# BG_LWOC_2_1.net
KiCad netlist of a schematic drawn in EAGLE
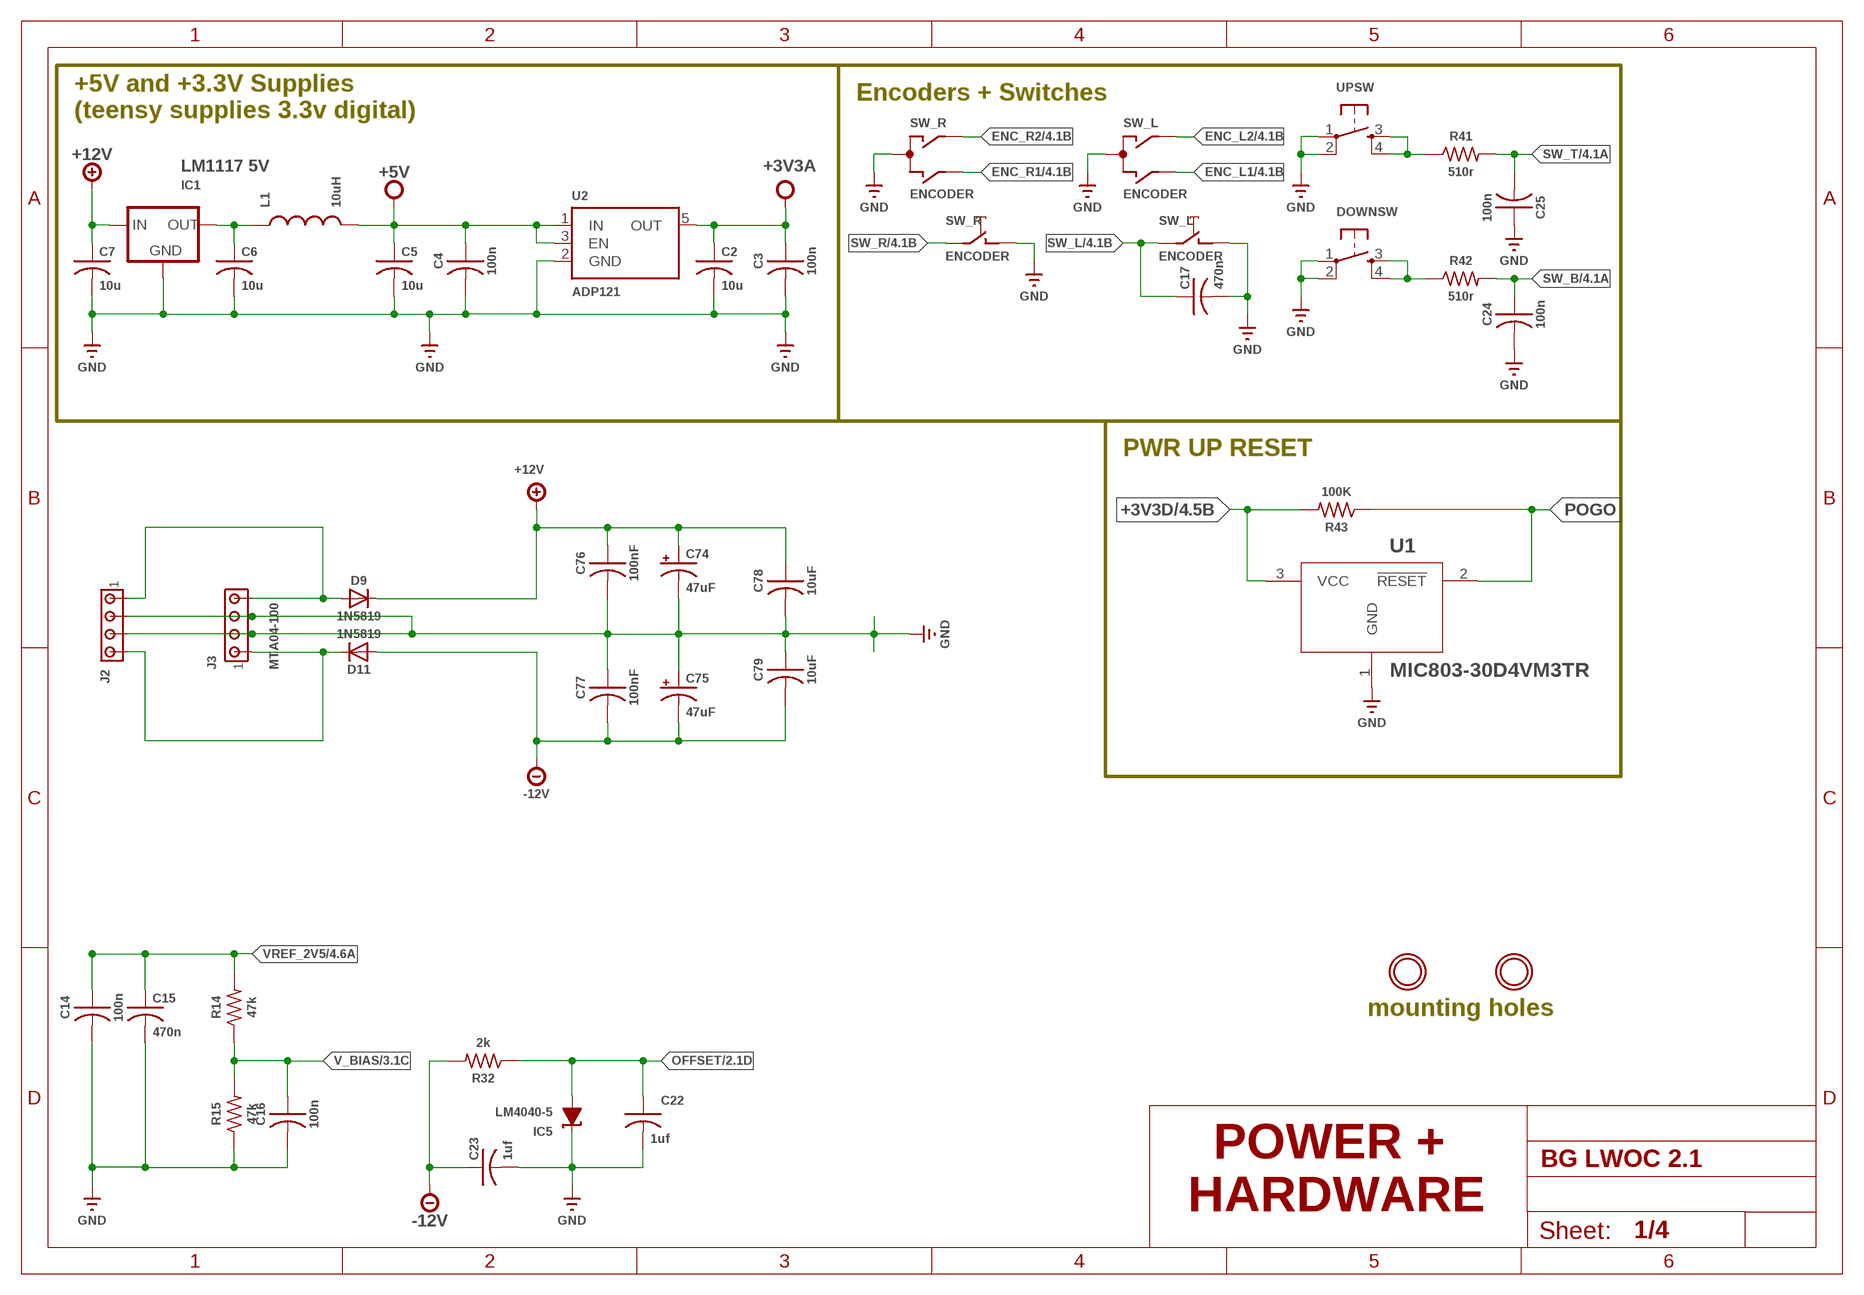
[diagram p0: schematic, sheet 1]
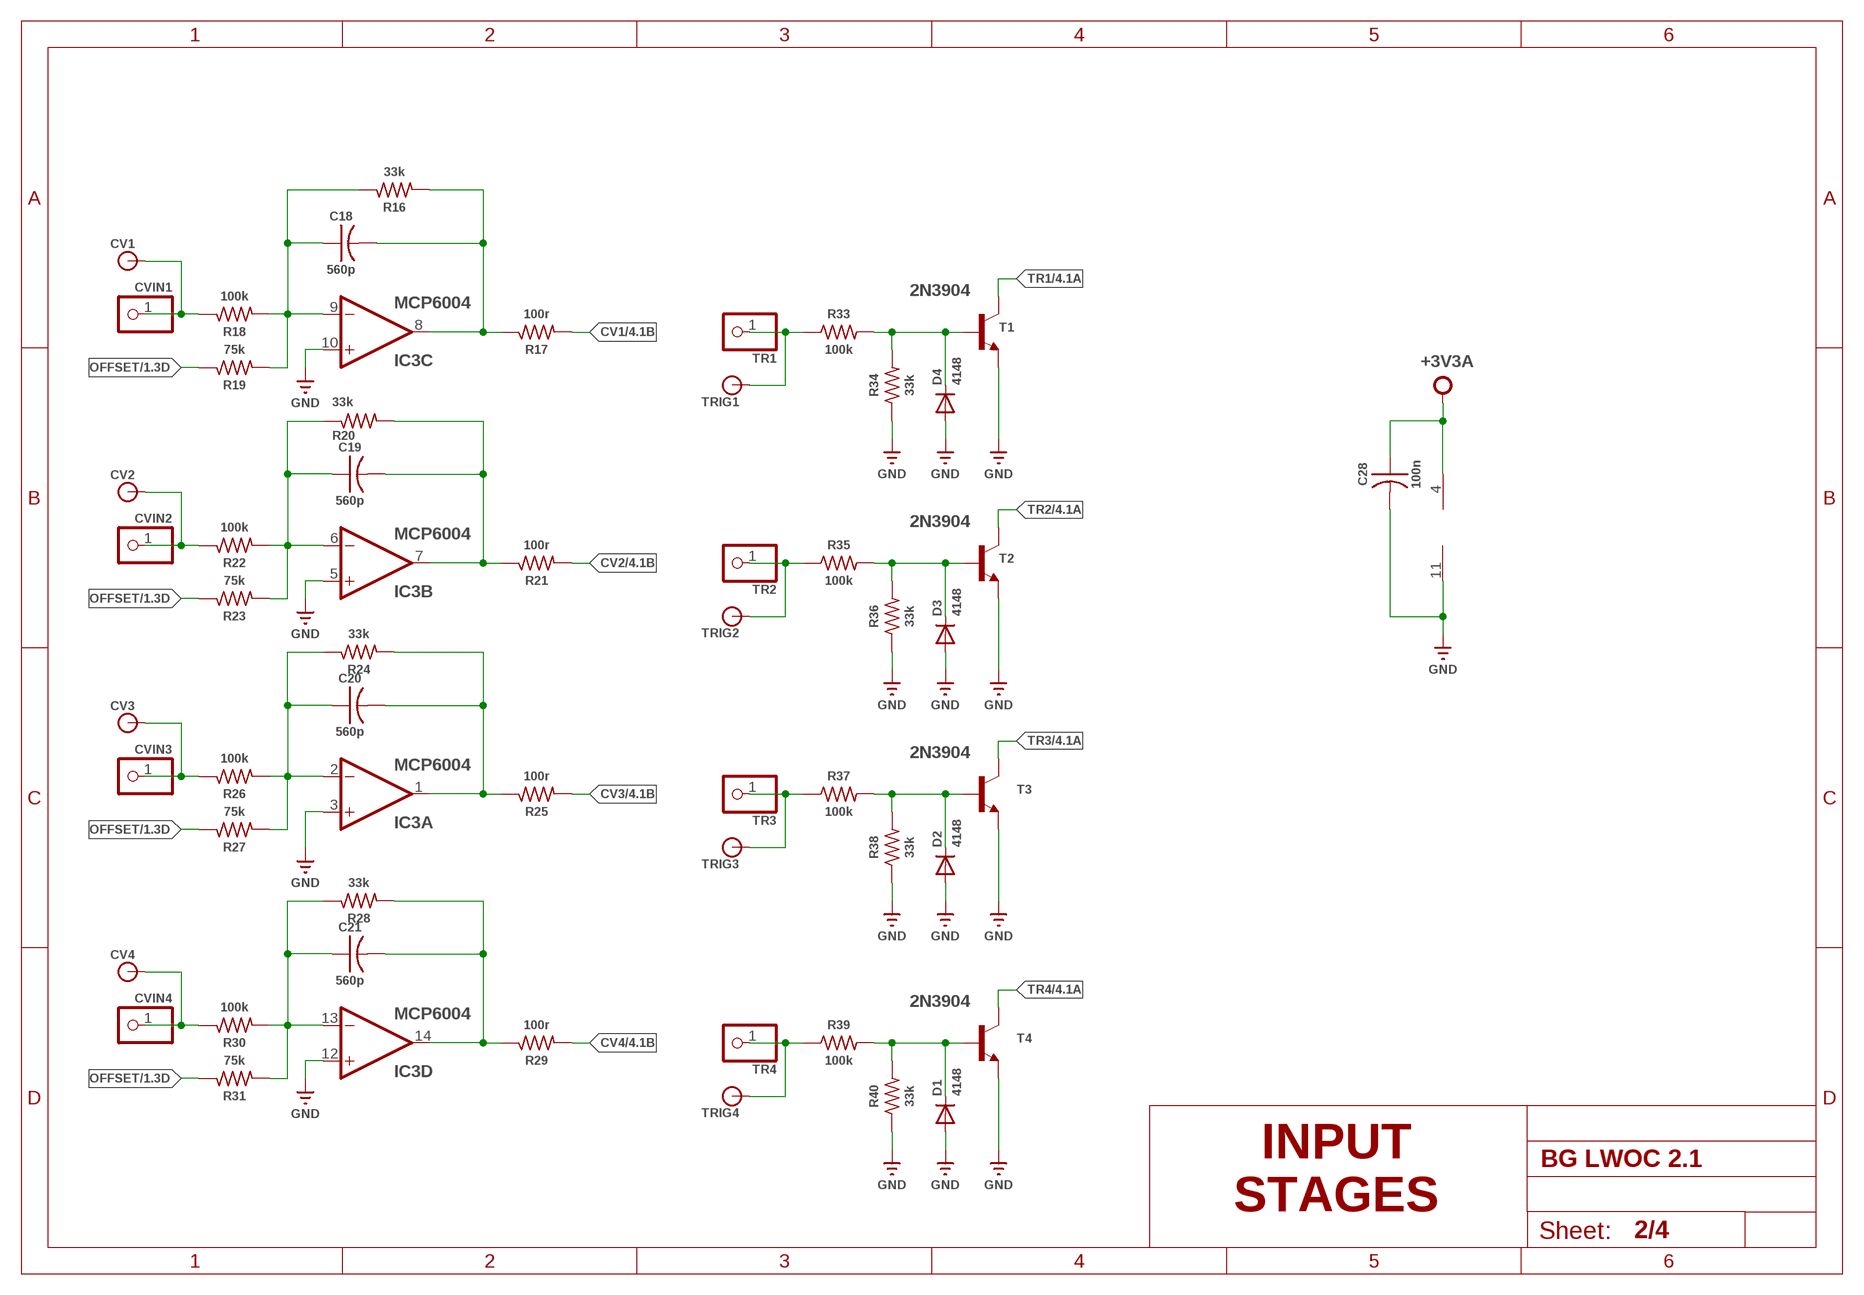
[diagram p1: schematic, sheet 2]
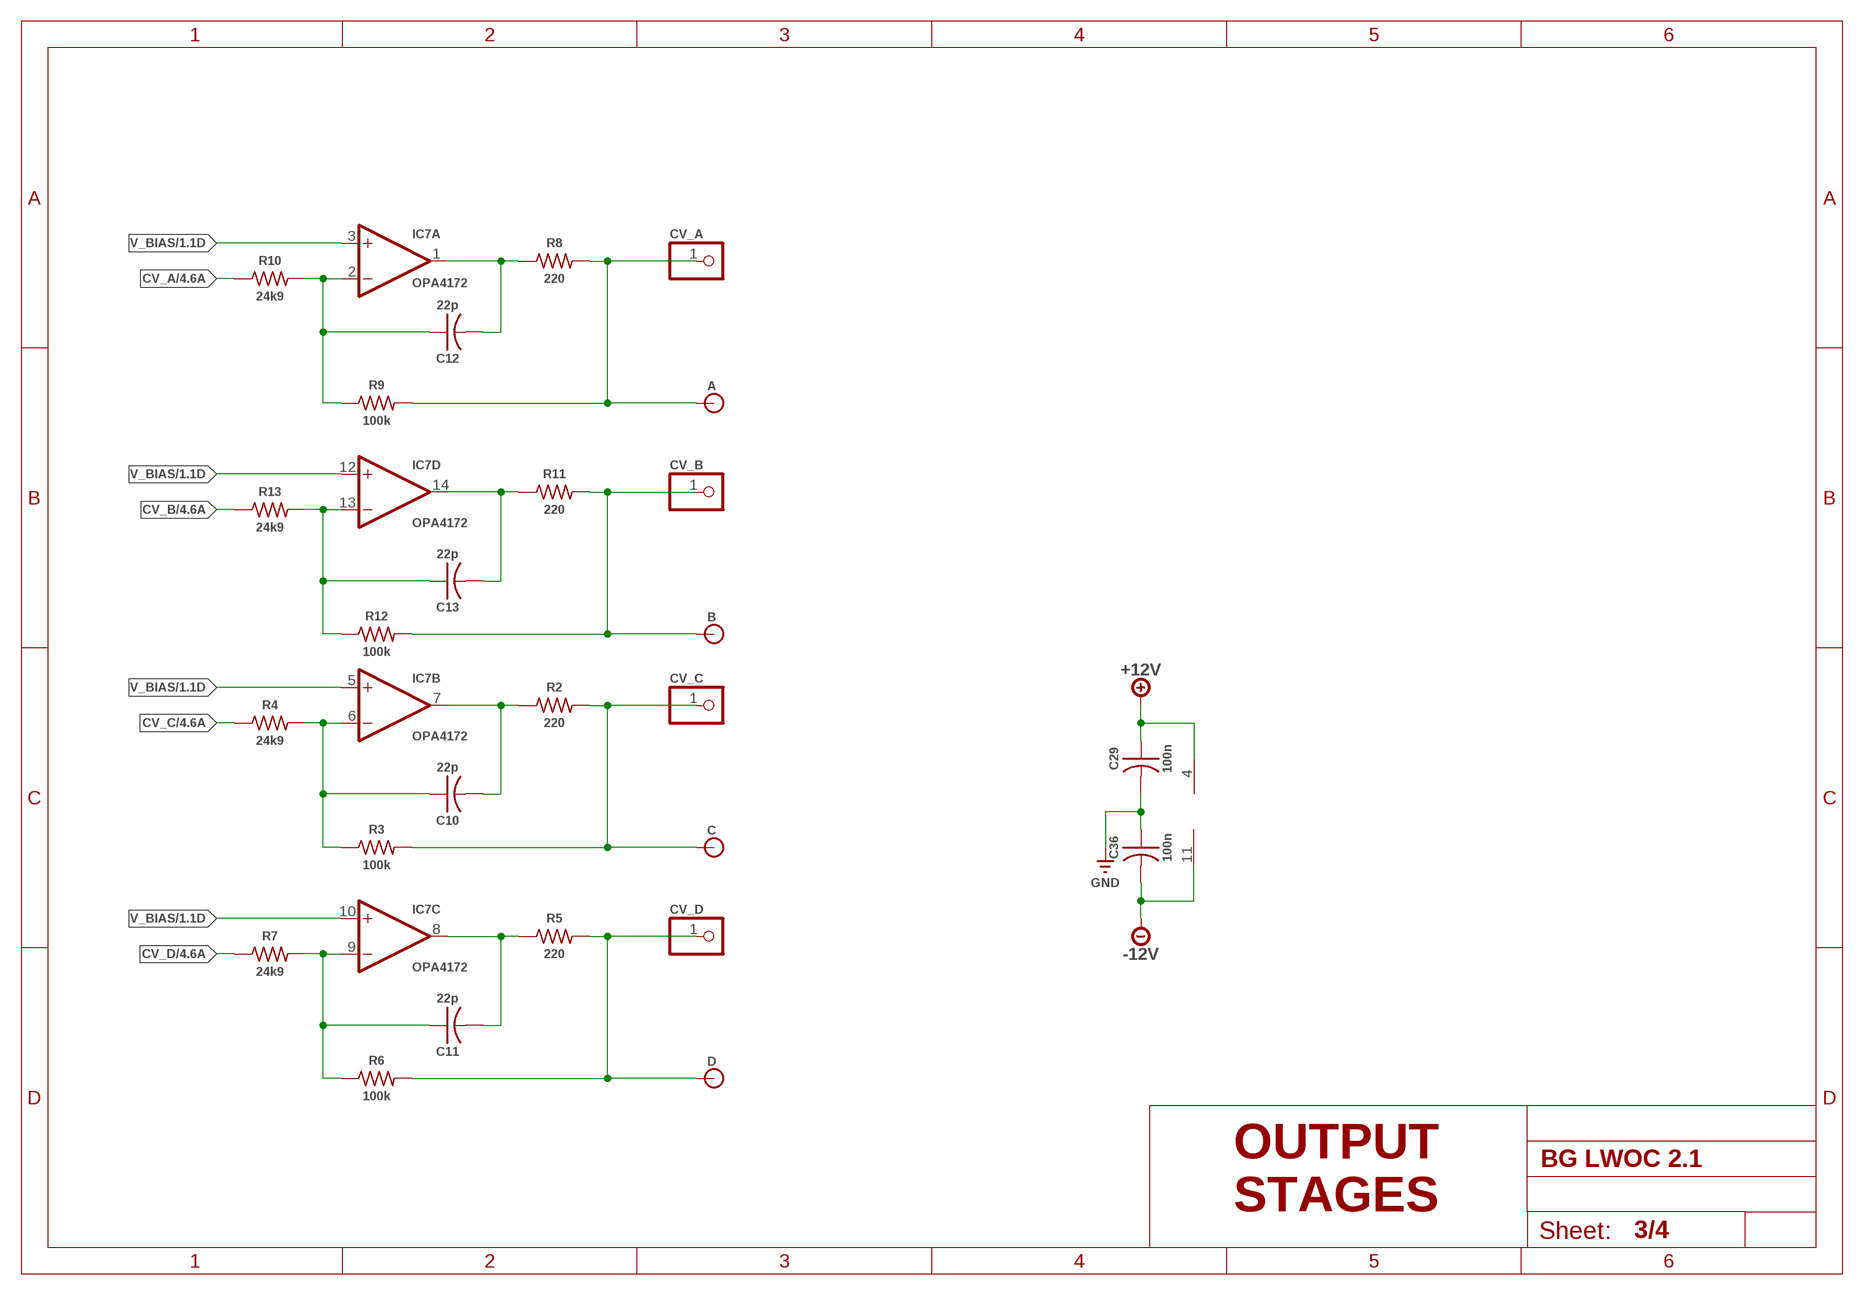
[diagram p2: schematic, sheet 3]
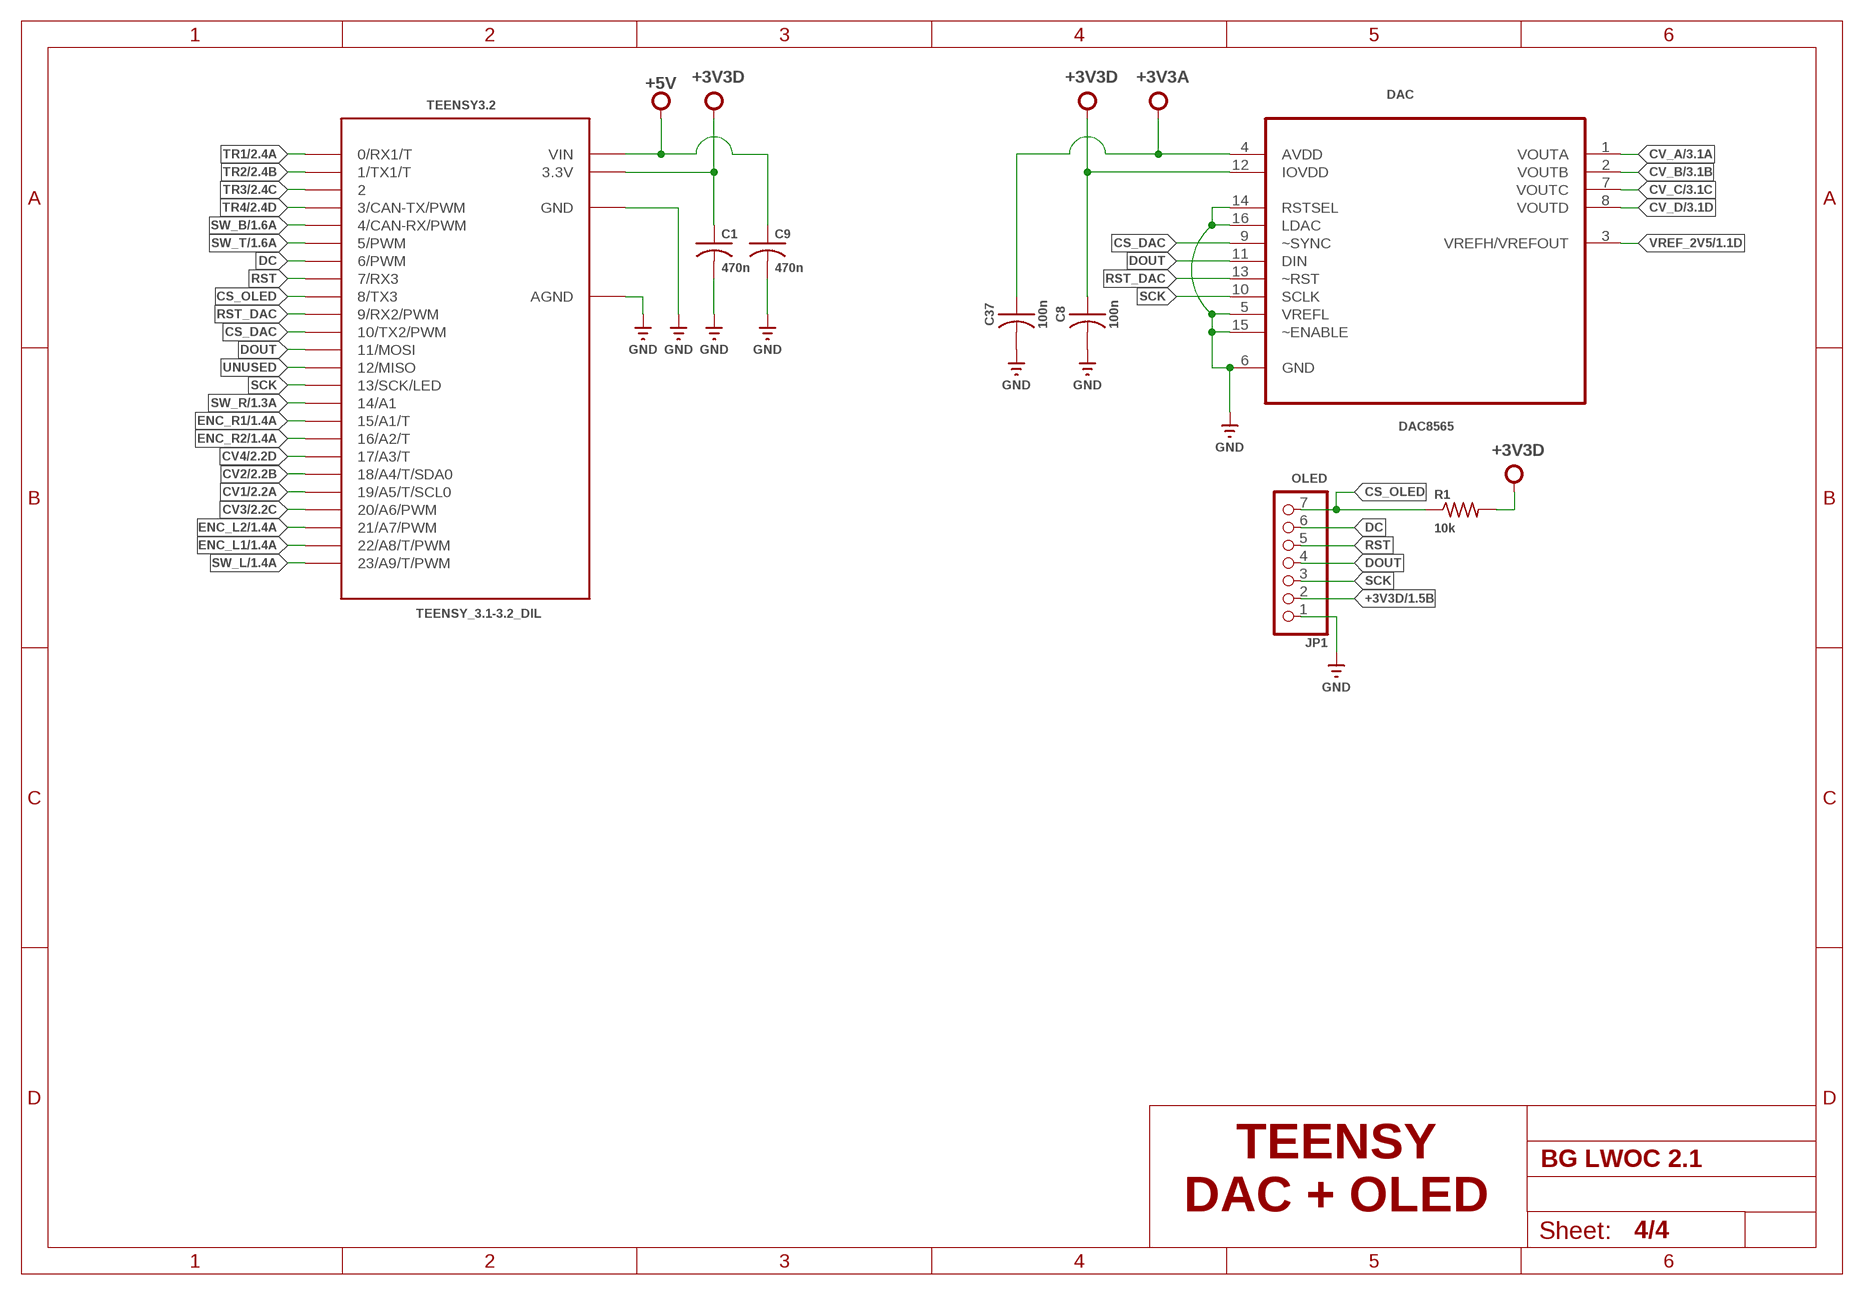
[diagram p3: schematic, sheet 4]

(export (version "E")
  (design (tool "Eeschema 10.0.6"))
  (components
    (comp (ref "C18")
      (value "560p")
      (footprint "eagle-import:RCL_C0603K")
      (libsource (lib "eagle-import") (part "RCL_C-USC0603K"))
    )
    (comp (ref "C19")
      (value "560p")
      (footprint "eagle-import:RCL_C0603K")
      (libsource (lib "eagle-import") (part "RCL_C-USC0603K"))
    )
    (comp (ref "C20")
      (value "560p")
      (footprint "eagle-import:RCL_C0603K")
      (libsource (lib "eagle-import") (part "RCL_C-USC0603K"))
    )
    (comp (ref "C21")
      (value "560p")
      (footprint "eagle-import:RCL_C0603K")
      (libsource (lib "eagle-import") (part "RCL_C-USC0603K"))
    )
    (comp (ref "C28")
      (value "100n")
      (footprint "eagle-import:RCL_C0603K")
      (libsource (lib "eagle-import") (part "RCL_C-USC0603K"))
    )
    (comp (ref "CV1")
      (value "BANANA_CONN")
      (footprint "eagle-import:BANANA_CONN")
      (libsource (lib "eagle-import") (part "BANANA_CONN"))
    )
    (comp (ref "CV2")
      (value "BANANA_CONN")
      (footprint "eagle-import:BANANA_CONN")
      (libsource (lib "eagle-import") (part "BANANA_CONN"))
    )
    (comp (ref "CV3")
      (value "BANANA_CONN")
      (footprint "eagle-import:BANANA_CONN")
      (libsource (lib "eagle-import") (part "BANANA_CONN"))
    )
    (comp (ref "CV4")
      (value "BANANA_CONN")
      (footprint "eagle-import:BANANA_CONN")
      (libsource (lib "eagle-import") (part "BANANA_CONN"))
    )
    (comp (ref "CVIN1")
      (value "PINHD-1X1")
      (footprint "eagle-import:1X01")
      (libsource (lib "eagle-import") (part "PINHD-1X1"))
    )
    (comp (ref "CVIN2")
      (value "PINHD-1X1")
      (footprint "eagle-import:1X01")
      (libsource (lib "eagle-import") (part "PINHD-1X1"))
    )
    (comp (ref "CVIN3")
      (value "PINHD-1X1")
      (footprint "eagle-import:1X01")
      (libsource (lib "eagle-import") (part "PINHD-1X1"))
    )
    (comp (ref "CVIN4")
      (value "PINHD-1X1")
      (footprint "eagle-import:1X01")
      (libsource (lib "eagle-import") (part "PINHD-1X1"))
    )
    (comp (ref "D1")
      (value "4148")
      (footprint "eagle-import:DIODE_SOD323-W")
      (libsource (lib "eagle-import") (part "DIODE_DIODE-SOD323-W"))
    )
    (comp (ref "D2")
      (value "4148")
      (footprint "eagle-import:DIODE_SOD323-W")
      (libsource (lib "eagle-import") (part "DIODE_DIODE-SOD323-W"))
    )
    (comp (ref "D3")
      (value "4148")
      (footprint "eagle-import:DIODE_SOD323-W")
      (libsource (lib "eagle-import") (part "DIODE_DIODE-SOD323-W"))
    )
    (comp (ref "D4")
      (value "4148")
      (footprint "eagle-import:DIODE_SOD323-W")
      (libsource (lib "eagle-import") (part "DIODE_DIODE-SOD323-W"))
    )
    (comp (ref "IC3")
      (value "MCP6004")
      (footprint "eagle-import:GM-ICS_SO14")
      (libsource (lib "eagle-import") (part "GM-ICS_TL074D"))
    )
    (comp (ref "R16")
      (value "33k")
      (footprint "eagle-import:RCL_R0603")
      (libsource (lib "eagle-import") (part "RCL_R-US_R0603"))
    )
    (comp (ref "R17")
      (value "100r")
      (footprint "eagle-import:RCL_R0603")
      (libsource (lib "eagle-import") (part "RCL_R-US_R0603"))
    )
    (comp (ref "R18")
      (value "100k")
      (footprint "eagle-import:RCL_R0603")
      (libsource (lib "eagle-import") (part "RCL_R-US_R0603"))
    )
    (comp (ref "R19")
      (value "75k")
      (footprint "eagle-import:RCL_R0603")
      (libsource (lib "eagle-import") (part "RCL_R-US_R0603"))
    )
    (comp (ref "R20")
      (value "33k")
      (footprint "eagle-import:RCL_R0603")
      (libsource (lib "eagle-import") (part "RCL_R-US_R0603"))
    )
    (comp (ref "R21")
      (value "100r")
      (footprint "eagle-import:RCL_R0603")
      (libsource (lib "eagle-import") (part "RCL_R-US_R0603"))
    )
    (comp (ref "R22")
      (value "100k")
      (footprint "eagle-import:RCL_R0603")
      (libsource (lib "eagle-import") (part "RCL_R-US_R0603"))
    )
    (comp (ref "R23")
      (value "75k")
      (footprint "eagle-import:RCL_R0603")
      (libsource (lib "eagle-import") (part "RCL_R-US_R0603"))
    )
    (comp (ref "R24")
      (value "33k")
      (footprint "eagle-import:RCL_R0603")
      (libsource (lib "eagle-import") (part "RCL_R-US_R0603"))
    )
    (comp (ref "R25")
      (value "100r")
      (footprint "eagle-import:RCL_R0603")
      (libsource (lib "eagle-import") (part "RCL_R-US_R0603"))
    )
    (comp (ref "R26")
      (value "100k")
      (footprint "eagle-import:RCL_R0603")
      (libsource (lib "eagle-import") (part "RCL_R-US_R0603"))
    )
    (comp (ref "R27")
      (value "75k")
      (footprint "eagle-import:RCL_R0603")
      (libsource (lib "eagle-import") (part "RCL_R-US_R0603"))
    )
    (comp (ref "R28")
      (value "33k")
      (footprint "eagle-import:RCL_R0603")
      (libsource (lib "eagle-import") (part "RCL_R-US_R0603"))
    )
    (comp (ref "R29")
      (value "100r")
      (footprint "eagle-import:RCL_R0603")
      (libsource (lib "eagle-import") (part "RCL_R-US_R0603"))
    )
    (comp (ref "R30")
      (value "100k")
      (footprint "eagle-import:RCL_R0603")
      (libsource (lib "eagle-import") (part "RCL_R-US_R0603"))
    )
    (comp (ref "R31")
      (value "75k")
      (footprint "eagle-import:RCL_R0603")
      (libsource (lib "eagle-import") (part "RCL_R-US_R0603"))
    )
    (comp (ref "R33")
      (value "100k")
      (footprint "eagle-import:RCL_R0603")
      (libsource (lib "eagle-import") (part "RCL_R-US_R0603"))
    )
    (comp (ref "R34")
      (value "33k")
      (footprint "eagle-import:RCL_R0603")
      (libsource (lib "eagle-import") (part "RCL_R-US_R0603"))
    )
    (comp (ref "R35")
      (value "100k")
      (footprint "eagle-import:RCL_R0603")
      (libsource (lib "eagle-import") (part "RCL_R-US_R0603"))
    )
    (comp (ref "R36")
      (value "33k")
      (footprint "eagle-import:RCL_R0603")
      (libsource (lib "eagle-import") (part "RCL_R-US_R0603"))
    )
    (comp (ref "R37")
      (value "100k")
      (footprint "eagle-import:RCL_R0603")
      (libsource (lib "eagle-import") (part "RCL_R-US_R0603"))
    )
    (comp (ref "R38")
      (value "33k")
      (footprint "eagle-import:RCL_R0603")
      (libsource (lib "eagle-import") (part "RCL_R-US_R0603"))
    )
    (comp (ref "R39")
      (value "100k")
      (footprint "eagle-import:RCL_R0603")
      (libsource (lib "eagle-import") (part "RCL_R-US_R0603"))
    )
    (comp (ref "R40")
      (value "33k")
      (footprint "eagle-import:RCL_R0603")
      (libsource (lib "eagle-import") (part "RCL_R-US_R0603"))
    )
    (comp (ref "T1")
      (value "2N3904")
      (footprint "eagle-import:TRANSISTOR_SOT23-BEC")
      (libsource (lib "eagle-import") (part "TRANSISTOR_-NPN-SOT23-BECMMBT3904LT1"))
    )
    (comp (ref "T2")
      (value "2N3904")
      (footprint "eagle-import:TRANSISTOR_SOT23-BEC")
      (libsource (lib "eagle-import") (part "TRANSISTOR_-NPN-SOT23-BECMMBT3904LT1"))
    )
    (comp (ref "T3")
      (value "2N3904")
      (footprint "eagle-import:TRANSISTOR_SOT23-BEC")
      (libsource (lib "eagle-import") (part "TRANSISTOR_-NPN-SOT23-BECMMBT3904LT1"))
    )
    (comp (ref "T4")
      (value "2N3904")
      (footprint "eagle-import:TRANSISTOR_SOT23-BEC")
      (libsource (lib "eagle-import") (part "TRANSISTOR_-NPN-SOT23-BECMMBT3904LT1"))
    )
    (comp (ref "TR1")
      (value "PINHD-1X1")
      (footprint "eagle-import:1X01")
      (libsource (lib "eagle-import") (part "PINHD-1X1"))
    )
    (comp (ref "TR2")
      (value "PINHD-1X1")
      (footprint "eagle-import:1X01")
      (libsource (lib "eagle-import") (part "PINHD-1X1"))
    )
    (comp (ref "TR3")
      (value "PINHD-1X1")
      (footprint "eagle-import:1X01")
      (libsource (lib "eagle-import") (part "PINHD-1X1"))
    )
    (comp (ref "TR4")
      (value "PINHD-1X1")
      (footprint "eagle-import:1X01")
      (libsource (lib "eagle-import") (part "PINHD-1X1"))
    )
    (comp (ref "TRIG1")
      (value "BANANA_CONN")
      (footprint "eagle-import:BANANA_CONN")
      (libsource (lib "eagle-import") (part "BANANA_CONN"))
    )
    (comp (ref "TRIG2")
      (value "BANANA_CONN")
      (footprint "eagle-import:BANANA_CONN")
      (libsource (lib "eagle-import") (part "BANANA_CONN"))
    )
    (comp (ref "TRIG3")
      (value "BANANA_CONN")
      (footprint "eagle-import:BANANA_CONN")
      (libsource (lib "eagle-import") (part "BANANA_CONN"))
    )
    (comp (ref "TRIG4")
      (value "BANANA_CONN")
      (footprint "eagle-import:BANANA_CONN")
      (libsource (lib "eagle-import") (part "BANANA_CONN"))
    )
    (comp (ref "A")
      (value "BANANA_CONN")
      (footprint "eagle-import:BANANA_CONN")
      (libsource (lib "eagle-import") (part "BANANA_CONN"))
    )
    (comp (ref "B")
      (value "BANANA_CONN")
      (footprint "eagle-import:BANANA_CONN")
      (libsource (lib "eagle-import") (part "BANANA_CONN"))
    )
    (comp (ref "C")
      (value "BANANA_CONN")
      (footprint "eagle-import:BANANA_CONN")
      (libsource (lib "eagle-import") (part "BANANA_CONN"))
    )
    (comp (ref "C10")
      (value "22p")
      (footprint "eagle-import:RCL_C0603K")
      (libsource (lib "eagle-import") (part "RCL_C-USC0603K"))
    )
    (comp (ref "C11")
      (value "22p")
      (footprint "eagle-import:RCL_C0603K")
      (libsource (lib "eagle-import") (part "RCL_C-USC0603K"))
    )
    (comp (ref "C12")
      (value "22p")
      (footprint "eagle-import:RCL_C0603K")
      (libsource (lib "eagle-import") (part "RCL_C-USC0603K"))
    )
    (comp (ref "C13")
      (value "22p")
      (footprint "eagle-import:RCL_C0603K")
      (libsource (lib "eagle-import") (part "RCL_C-USC0603K"))
    )
    (comp (ref "C29")
      (value "100n")
      (footprint "eagle-import:RCL_C0603K")
      (libsource (lib "eagle-import") (part "RCL_C-USC0603K"))
    )
    (comp (ref "C36")
      (value "100n")
      (footprint "eagle-import:RCL_C0603K")
      (libsource (lib "eagle-import") (part "RCL_C-USC0603K"))
    )
    (comp (ref "CV_A")
      (value "PINHD-1X1")
      (footprint "eagle-import:1X01")
      (libsource (lib "eagle-import") (part "PINHD-1X1"))
    )
    (comp (ref "CV_B")
      (value "PINHD-1X1")
      (footprint "eagle-import:1X01")
      (libsource (lib "eagle-import") (part "PINHD-1X1"))
    )
    (comp (ref "CV_C")
      (value "PINHD-1X1")
      (footprint "eagle-import:1X01")
      (libsource (lib "eagle-import") (part "PINHD-1X1"))
    )
    (comp (ref "CV_D")
      (value "PINHD-1X1")
      (footprint "eagle-import:1X01")
      (libsource (lib "eagle-import") (part "PINHD-1X1"))
    )
    (comp (ref "D")
      (value "BANANA_CONN")
      (footprint "eagle-import:BANANA_CONN")
      (libsource (lib "eagle-import") (part "BANANA_CONN"))
    )
    (comp (ref "IC7")
      (value "OPA4172")
      (footprint "eagle-import:GM-ICS_SO14")
      (libsource (lib "eagle-import") (part "GM-ICS_TL074D"))
    )
    (comp (ref "R2")
      (value "220")
      (footprint "eagle-import:RCL_R0603")
      (libsource (lib "eagle-import") (part "RCL_R-US_R0603"))
    )
    (comp (ref "R3")
      (value "100k")
      (footprint "eagle-import:RCL_R0603")
      (libsource (lib "eagle-import") (part "RCL_R-US_R0603"))
    )
    (comp (ref "R4")
      (value "24k9")
      (footprint "eagle-import:RCL_R0603")
      (libsource (lib "eagle-import") (part "RCL_R-US_R0603"))
    )
    (comp (ref "R5")
      (value "220")
      (footprint "eagle-import:RCL_R0603")
      (libsource (lib "eagle-import") (part "RCL_R-US_R0603"))
    )
    (comp (ref "R6")
      (value "100k")
      (footprint "eagle-import:RCL_R0603")
      (libsource (lib "eagle-import") (part "RCL_R-US_R0603"))
    )
    (comp (ref "R7")
      (value "24k9")
      (footprint "eagle-import:RCL_R0603")
      (libsource (lib "eagle-import") (part "RCL_R-US_R0603"))
    )
    (comp (ref "R8")
      (value "220")
      (footprint "eagle-import:RCL_R0603")
      (libsource (lib "eagle-import") (part "RCL_R-US_R0603"))
    )
    (comp (ref "R9")
      (value "100k")
      (footprint "eagle-import:RCL_R0603")
      (libsource (lib "eagle-import") (part "RCL_R-US_R0603"))
    )
    (comp (ref "R10")
      (value "24k9")
      (footprint "eagle-import:RCL_R0603")
      (libsource (lib "eagle-import") (part "RCL_R-US_R0603"))
    )
    (comp (ref "R11")
      (value "220")
      (footprint "eagle-import:RCL_R0603")
      (libsource (lib "eagle-import") (part "RCL_R-US_R0603"))
    )
    (comp (ref "R12")
      (value "100k")
      (footprint "eagle-import:RCL_R0603")
      (libsource (lib "eagle-import") (part "RCL_R-US_R0603"))
    )
    (comp (ref "R13")
      (value "24k9")
      (footprint "eagle-import:RCL_R0603")
      (libsource (lib "eagle-import") (part "RCL_R-US_R0603"))
    )
    (comp (ref "C2")
      (value "10u")
      (footprint "eagle-import:C1206K")
      (libsource (lib "eagle-import") (part "C-USC1206K"))
    )
    (comp (ref "C3")
      (value "100n")
      (footprint "eagle-import:RCL_C0603K")
      (libsource (lib "eagle-import") (part "RCL_C-USC0603K"))
    )
    (comp (ref "C4")
      (value "100n")
      (footprint "eagle-import:RCL_C0603K")
      (libsource (lib "eagle-import") (part "RCL_C-USC0603K"))
    )
    (comp (ref "C5")
      (value "10u")
      (footprint "eagle-import:C1206K")
      (libsource (lib "eagle-import") (part "C-USC1206K"))
    )
    (comp (ref "C6")
      (value "10u")
      (footprint "eagle-import:C1206K")
      (libsource (lib "eagle-import") (part "C-USC1206K"))
    )
    (comp (ref "C7")
      (value "10u")
      (footprint "eagle-import:C1206K")
      (libsource (lib "eagle-import") (part "C-USC1206K"))
    )
    (comp (ref "C14")
      (value "100n")
      (footprint "eagle-import:RCL_C0603K")
      (libsource (lib "eagle-import") (part "RCL_C-USC0603K"))
    )
    (comp (ref "C15")
      (value "470n")
      (footprint "eagle-import:RCL_C0603K")
      (libsource (lib "eagle-import") (part "RCL_C-USC0603K"))
    )
    (comp (ref "C16")
      (value "100n")
      (footprint "eagle-import:RCL_C0603K")
      (libsource (lib "eagle-import") (part "RCL_C-USC0603K"))
    )
    (comp (ref "C17")
      (value "470n")
      (footprint "eagle-import:C0805K")
      (libsource (lib "eagle-import") (part "C-USC0805K"))
    )
    (comp (ref "C22")
      (value "1uf")
      (footprint "eagle-import:C0805K")
      (libsource (lib "eagle-import") (part "C-USC0805K"))
    )
    (comp (ref "C23")
      (value "1uf")
      (footprint "eagle-import:C0805K")
      (libsource (lib "eagle-import") (part "C-USC0805K"))
    )
    (comp (ref "C24")
      (value "100n")
      (footprint "eagle-import:RCL_C0603K")
      (libsource (lib "eagle-import") (part "RCL_C-USC0603K"))
    )
    (comp (ref "C25")
      (value "100n")
      (footprint "eagle-import:RCL_C0603K")
      (libsource (lib "eagle-import") (part "RCL_C-USC0603K"))
    )
    (comp (ref "C74")
      (value "47uF")
      (footprint "eagle-import:RCL_E2,5-6")
      (libsource (lib "eagle-import") (part "RCL_CPOL-USE2.5-6"))
    )
    (comp (ref "C75")
      (value "47uF")
      (footprint "eagle-import:RCL_E2,5-6")
      (libsource (lib "eagle-import") (part "RCL_CPOL-USE2.5-6"))
    )
    (comp (ref "C76")
      (value "100nF")
      (footprint "eagle-import:RCL_C0603K")
      (libsource (lib "eagle-import") (part "ripples_v40_RCL_C-USC0603K"))
    )
    (comp (ref "C77")
      (value "100nF")
      (footprint "eagle-import:RCL_C0603K")
      (libsource (lib "eagle-import") (part "ripples_v40_RCL_C-USC0603K"))
    )
    (comp (ref "C78")
      (value "10uF")
      (footprint "eagle-import:RCL_C1210")
      (libsource (lib "eagle-import") (part "RCL_C-USC1210"))
    )
    (comp (ref "C79")
      (value "10uF")
      (footprint "eagle-import:RCL_C1210")
      (libsource (lib "eagle-import") (part "RCL_C-USC1210"))
    )
    (comp (ref "D9")
      (value "1N5819")
      (footprint "eagle-import:DIODE_SOD323-W")
      (libsource (lib "eagle-import") (part "ripples_v40_DIODE_DIODE-SOD323-W"))
    )
    (comp (ref "D11")
      (value "1N5819")
      (footprint "eagle-import:DIODE_SOD323-W")
      (libsource (lib "eagle-import") (part "ripples_v40_DIODE_DIODE-SOD323-W"))
    )
    (comp (ref "DOWNSW")
      (value "SPARKFUN_TAC_SWITCHPTH")
      (footprint "eagle-import:SPARKFUN_TACTILE-PTH")
      (libsource (lib "eagle-import") (part "SPARKFUN_TAC_SWITCHPTH"))
    )
    (comp (ref "IC1")
      (value "LM1117 5V")
      (footprint "eagle-import:TO252")
      (libsource (lib "eagle-import") (part "LM1117TO252"))
    )
    (comp (ref "IC5")
      (value "LM4040-5")
      (footprint "eagle-import:DBZ_R-PDSO-G3")
      (libsource (lib "eagle-import") (part "LM4041DBZA12"))
    )
    (comp (ref "J2")
      (value "MTA04-156")
      (footprint "eagle-import:1X4MTA")
      (libsource (lib "eagle-import") (part "MTA04-156"))
    )
    (comp (ref "J3")
      (value "MTA04-100")
      (footprint "eagle-import:1X04MTA")
      (libsource (lib "eagle-import") (part "MTA04-100"))
    )
    (comp (ref "L1")
      (value "10uH")
      (footprint "eagle-import:1210")
      (libsource (lib "eagle-import") (part "INDUCTOR1210"))
    )
    (comp (ref "R14")
      (value "47k")
      (footprint "eagle-import:RCL_R0603")
      (libsource (lib "eagle-import") (part "RCL_R-US_R0603"))
    )
    (comp (ref "R15")
      (value "47k")
      (footprint "eagle-import:RCL_R0603")
      (libsource (lib "eagle-import") (part "RCL_R-US_R0603"))
    )
    (comp (ref "R32")
      (value "2k")
      (footprint "eagle-import:RCL_R0603")
      (libsource (lib "eagle-import") (part "RCL_R-US_R0603"))
    )
    (comp (ref "R41")
      (value "510r")
      (footprint "eagle-import:RCL_R0603")
      (libsource (lib "eagle-import") (part "RCL_R-US_R0603"))
    )
    (comp (ref "R42")
      (value "510r")
      (footprint "eagle-import:RCL_R0603")
      (libsource (lib "eagle-import") (part "RCL_R-US_R0603"))
    )
    (comp (ref "R43")
      (value "100K")
      (footprint "eagle-import:RCL_R0603")
      (libsource (lib "eagle-import") (part "RCL_R-US_R0603"))
    )
    (comp (ref "SW_L")
      (value "ENCODER")
      (footprint "eagle-import:OG-ENCODER_ALPS_EC12E_SW")
      (libsource (lib "eagle-import") (part "OG-ENCODER_EC12E_SW"))
    )
    (comp (ref "SW_R")
      (value "ENCODER")
      (footprint "eagle-import:OG-ENCODER_ALPS_EC12E_SW")
      (libsource (lib "eagle-import") (part "OG-ENCODER_EC12E_SW"))
    )
    (comp (ref "U$23")
      (value "MOUNTINGHOLE2.5")
      (footprint "eagle-import:MOUNTINGHOLE_2.5_PLATED")
      (libsource (lib "eagle-import") (part "MOUNTINGHOLE2.5"))
    )
    (comp (ref "U$26")
      (value "MOUNTINGHOLE2.5")
      (footprint "eagle-import:MOUNTINGHOLE_2.5_PLATED")
      (libsource (lib "eagle-import") (part "MOUNTINGHOLE2.5"))
    )
    (comp (ref "U1")
      (value "MIC803-30D4VM3TR")
      (footprint "eagle-import:SOT95P232X110-3N")
      (libsource (lib "eagle-import") (part "MIC803-30D4VM3TR"))
    )
    (comp (ref "U2")
      (value "ADP121")
      (footprint "eagle-import:SOT23-5")
      (libsource (lib "eagle-import") (part "ADP121"))
    )
    (comp (ref "UPSW")
      (value "SPARKFUN_TAC_SWITCHPTH")
      (footprint "eagle-import:SPARKFUN_TACTILE-PTH")
      (libsource (lib "eagle-import") (part "SPARKFUN_TAC_SWITCHPTH"))
    )
    (comp (ref "C1")
      (value "470n")
      (footprint "eagle-import:C0805K")
      (libsource (lib "eagle-import") (part "C-USC0805K"))
    )
    (comp (ref "C8")
      (value "100n")
      (footprint "eagle-import:RCL_C0603K")
      (libsource (lib "eagle-import") (part "RCL_C-USC0603K"))
    )
    (comp (ref "C9")
      (value "470n")
      (footprint "eagle-import:C0805K")
      (libsource (lib "eagle-import") (part "C-USC0805K"))
    )
    (comp (ref "C37")
      (value "100n")
      (footprint "eagle-import:RCL_C0603K")
      (libsource (lib "eagle-import") (part "RCL_C-USC0603K"))
    )
    (comp (ref "DAC")
      (value "DAC8565")
      (footprint "eagle-import:SOP65P640X120-16N")
      (fields (field (name "MF") "Texas Instruments") (field (name "MP") "DAC8565IAPW"))
      (libsource (lib "eagle-import") (part "DAC8565IAPW"))
    )
    (comp (ref "JP1")
      (value "OLED")
      (footprint "eagle-import:1X07")
      (libsource (lib "eagle-import") (part "PINHD-1X7"))
    )
    (comp (ref "R1")
      (value "10k")
      (footprint "eagle-import:M0805")
      (libsource (lib "eagle-import") (part "R-US_M0805"))
    )
    (comp (ref "TEENSY3.2")
      (value "TEENSY_3.1-3.2_DIL")
      (footprint "eagle-import:TEENSY_3.0-3.2&LC_DIL")
      (libsource (lib "eagle-import") (part "TEENSY_3.1-3.2_DIL"))
    )
  )
  (nets
    (net (code "1") (name "+3V3A") (class "Default")
      (node (ref "C2") (pin "1") (pinfunction "1_1") (pintype "passive"))
      (node (ref "C28") (pin "1") (pinfunction "1_1") (pintype "passive"))
      (node (ref "C3") (pin "1") (pinfunction "1_1") (pintype "passive"))
      (node (ref "C37") (pin "1") (pinfunction "1_1") (pintype "passive"))
      (node (ref "DAC") (pin "4") (pinfunction "AVDD_4") (pintype "power_in"))
      (node (ref "IC3") (pin "4") (pinfunction "V+_4") (pintype "power_in"))
      (node (ref "U2") (pin "5") (pinfunction "OUT_5") (pintype "bidirectional"))
    )
    (net (code "2") (name "+3V3D") (class "Default")
      (node (ref "C1") (pin "1") (pinfunction "1_1") (pintype "passive"))
      (node (ref "C8") (pin "1") (pinfunction "1_1") (pintype "passive"))
      (node (ref "DAC") (pin "12") (pinfunction "IOVDD_12") (pintype "power_in"))
      (node (ref "JP1") (pin "2") (pinfunction "2_2") (pintype "passive"))
      (node (ref "R1") (pin "2") (pinfunction "2_2") (pintype "passive"))
      (node (ref "R43") (pin "2") (pinfunction "2_2") (pintype "passive"))
      (node (ref "TEENSY3.2") (pin "3.3V") (pinfunction "3.3V_3.3V") (pintype "power_in"))
      (node (ref "U1") (pin "3") (pinfunction "VCC_3") (pintype "power_in"))
    )
    (net (code "3") (name "+5V") (class "Default")
      (node (ref "C4") (pin "1") (pinfunction "1_1") (pintype "passive"))
      (node (ref "C5") (pin "1") (pinfunction "1_1") (pintype "passive"))
      (node (ref "C9") (pin "1") (pinfunction "1_1") (pintype "passive"))
      (node (ref "L1") (pin "2") (pinfunction "2_2") (pintype "passive"))
      (node (ref "TEENSY3.2") (pin "VIN") (pinfunction "VIN_VIN") (pintype "power_in"))
      (node (ref "U2") (pin "1") (pinfunction "IN_1") (pintype "bidirectional"))
      (node (ref "U2") (pin "3") (pinfunction "EN_3") (pintype "bidirectional"))
    )
    (net (code "4") (name "+12V") (class "Default")
      (node (ref "C29") (pin "1") (pinfunction "1_1") (pintype "passive"))
      (node (ref "C7") (pin "1") (pinfunction "1_1") (pintype "passive"))
      (node (ref "C74") (pin "+") (pinfunction "+_+") (pintype "passive"))
      (node (ref "C76") (pin "1") (pinfunction "1_1") (pintype "passive"))
      (node (ref "C78") (pin "1") (pinfunction "1_1") (pintype "passive"))
      (node (ref "D9") (pin "C") (pinfunction "C_C") (pintype "passive"))
      (node (ref "IC1") (pin "2") (pinfunction "IN_2") (pintype "input"))
      (node (ref "IC7") (pin "4") (pinfunction "V+_4") (pintype "power_in"))
    )
    (net (code "5") (name "-12V") (class "Default")
      (node (ref "C23") (pin "1") (pinfunction "1_1") (pintype "passive"))
      (node (ref "C36") (pin "2") (pinfunction "2_2") (pintype "passive"))
      (node (ref "C75") (pin "-") (pinfunction "-_-") (pintype "passive"))
      (node (ref "C77") (pin "2") (pinfunction "2_2") (pintype "passive"))
      (node (ref "C79") (pin "2") (pinfunction "2_2") (pintype "passive"))
      (node (ref "D11") (pin "A") (pinfunction "A_A") (pintype "passive"))
      (node (ref "IC7") (pin "11") (pinfunction "V-_11") (pintype "power_in"))
      (node (ref "R32") (pin "2") (pinfunction "2_2") (pintype "passive"))
    )
    (net (code "6") (name "CS_DAC") (class "Default")
      (node (ref "DAC") (pin "9") (pinfunction "~{SYNC}_9") (pintype "input"))
      (node (ref "TEENSY3.2") (pin "10") (pinfunction "10/TX2/PWM_10") (pintype "bidirectional"))
    )
    (net (code "7") (name "CS_OLED") (class "Default")
      (node (ref "JP1") (pin "7") (pinfunction "7_7") (pintype "passive"))
      (node (ref "R1") (pin "1") (pinfunction "1_1") (pintype "passive"))
      (node (ref "TEENSY3.2") (pin "8") (pinfunction "8/TX3_8") (pintype "bidirectional"))
    )
    (net (code "8") (name "CV1") (class "Default")
      (node (ref "R17") (pin "2") (pinfunction "2_2") (pintype "passive"))
      (node (ref "TEENSY3.2") (pin "19/A5") (pinfunction "19/A5/T/SCL0_19/A5") (pintype "bidirectional"))
    )
    (net (code "9") (name "CV2") (class "Default")
      (node (ref "R21") (pin "2") (pinfunction "2_2") (pintype "passive"))
      (node (ref "TEENSY3.2") (pin "18/A4") (pinfunction "18/A4/T/SDA0_18/A4") (pintype "bidirectional"))
    )
    (net (code "10") (name "CV3") (class "Default")
      (node (ref "R25") (pin "2") (pinfunction "2_2") (pintype "passive"))
      (node (ref "TEENSY3.2") (pin "20/A6") (pinfunction "20/A6/PWM_20/A6") (pintype "bidirectional"))
    )
    (net (code "11") (name "CV4") (class "Default")
      (node (ref "R29") (pin "2") (pinfunction "2_2") (pintype "passive"))
      (node (ref "TEENSY3.2") (pin "17/A3") (pinfunction "17/A3/T_17/A3") (pintype "bidirectional"))
    )
    (net (code "12") (name "CV_A") (class "Default")
      (node (ref "DAC") (pin "1") (pinfunction "VOUTA_1") (pintype "output"))
      (node (ref "R10") (pin "1") (pinfunction "1_1") (pintype "passive"))
    )
    (net (code "13") (name "CV_B") (class "Default")
      (node (ref "DAC") (pin "2") (pinfunction "VOUTB_2") (pintype "output"))
      (node (ref "R13") (pin "1") (pinfunction "1_1") (pintype "passive"))
    )
    (net (code "14") (name "CV_C") (class "Default")
      (node (ref "DAC") (pin "7") (pinfunction "VOUTC_7") (pintype "output"))
      (node (ref "R4") (pin "1") (pinfunction "1_1") (pintype "passive"))
    )
    (net (code "15") (name "CV_D") (class "Default")
      (node (ref "DAC") (pin "8") (pinfunction "VOUTD_8") (pintype "output"))
      (node (ref "R7") (pin "1") (pinfunction "1_1") (pintype "passive"))
    )
    (net (code "16") (name "DC") (class "Default")
      (node (ref "JP1") (pin "6") (pinfunction "6_6") (pintype "passive"))
      (node (ref "TEENSY3.2") (pin "6") (pinfunction "6/PWM_6") (pintype "bidirectional"))
    )
    (net (code "17") (name "DOUT") (class "Default")
      (node (ref "DAC") (pin "11") (pinfunction "DIN_11") (pintype "input"))
      (node (ref "JP1") (pin "4") (pinfunction "4_4") (pintype "passive"))
      (node (ref "TEENSY3.2") (pin "11") (pinfunction "11/MOSI_11") (pintype "bidirectional"))
    )
    (net (code "18") (name "ENC_L1") (class "Default")
      (node (ref "SW_L") (pin "B") (pinfunction "B_B") (pintype "passive"))
      (node (ref "TEENSY3.2") (pin "22/A8") (pinfunction "22/A8/T/PWM_22/A8") (pintype "bidirectional"))
    )
    (net (code "19") (name "ENC_L2") (class "Default")
      (node (ref "SW_L") (pin "A") (pinfunction "A_A") (pintype "passive"))
      (node (ref "TEENSY3.2") (pin "21/A7") (pinfunction "21/A7/PWM_21/A7") (pintype "bidirectional"))
    )
    (net (code "20") (name "ENC_R1") (class "Default")
      (node (ref "SW_R") (pin "B") (pinfunction "B_B") (pintype "passive"))
      (node (ref "TEENSY3.2") (pin "15/A1") (pinfunction "15/A1/T_15/A1") (pintype "bidirectional"))
    )
    (net (code "21") (name "ENC_R2") (class "Default")
      (node (ref "SW_R") (pin "A") (pinfunction "A_A") (pintype "passive"))
      (node (ref "TEENSY3.2") (pin "16/A2") (pinfunction "16/A2/T_16/A2") (pintype "bidirectional"))
    )
    (net (code "22") (name "GND") (class "Default")
      (node (ref "C1") (pin "2") (pinfunction "2_2") (pintype "passive"))
      (node (ref "C14") (pin "2") (pinfunction "2_2") (pintype "passive"))
      (node (ref "C15") (pin "2") (pinfunction "2_2") (pintype "passive"))
      (node (ref "C16") (pin "2") (pinfunction "2_2") (pintype "passive"))
      (node (ref "C17") (pin "2") (pinfunction "2_2") (pintype "passive"))
      (node (ref "C2") (pin "2") (pinfunction "2_2") (pintype "passive"))
      (node (ref "C22") (pin "2") (pinfunction "2_2") (pintype "passive"))
      (node (ref "C23") (pin "2") (pinfunction "2_2") (pintype "passive"))
      (node (ref "C24") (pin "2") (pinfunction "2_2") (pintype "passive"))
      (node (ref "C25") (pin "1") (pinfunction "1_1") (pintype "passive"))
      (node (ref "C28") (pin "2") (pinfunction "2_2") (pintype "passive"))
      (node (ref "C29") (pin "2") (pinfunction "2_2") (pintype "passive"))
      (node (ref "C3") (pin "2") (pinfunction "2_2") (pintype "passive"))
      (node (ref "C36") (pin "1") (pinfunction "1_1") (pintype "passive"))
      (node (ref "C37") (pin "2") (pinfunction "2_2") (pintype "passive"))
      (node (ref "C4") (pin "2") (pinfunction "2_2") (pintype "passive"))
      (node (ref "C5") (pin "2") (pinfunction "2_2") (pintype "passive"))
      (node (ref "C6") (pin "2") (pinfunction "2_2") (pintype "passive"))
      (node (ref "C7") (pin "2") (pinfunction "2_2") (pintype "passive"))
      (node (ref "C74") (pin "-") (pinfunction "-_-") (pintype "passive"))
      (node (ref "C75") (pin "+") (pinfunction "+_+") (pintype "passive"))
      (node (ref "C76") (pin "2") (pinfunction "2_2") (pintype "passive"))
      (node (ref "C77") (pin "1") (pinfunction "1_1") (pintype "passive"))
      (node (ref "C78") (pin "2") (pinfunction "2_2") (pintype "passive"))
      (node (ref "C79") (pin "1") (pinfunction "1_1") (pintype "passive"))
      (node (ref "C8") (pin "2") (pinfunction "2_2") (pintype "passive"))
      (node (ref "C9") (pin "2") (pinfunction "2_2") (pintype "passive"))
      (node (ref "D1") (pin "A") (pinfunction "A_A") (pintype "passive"))
      (node (ref "D2") (pin "A") (pinfunction "A_A") (pintype "passive"))
      (node (ref "D3") (pin "A") (pinfunction "A_A") (pintype "passive"))
      (node (ref "D4") (pin "A") (pinfunction "A_A") (pintype "passive"))
      (node (ref "DAC") (pin "14") (pinfunction "RSTSEL_14") (pintype "input"))
      (node (ref "DAC") (pin "15") (pinfunction "~{ENABLE}_15") (pintype "input"))
      (node (ref "DAC") (pin "16") (pinfunction "LDAC_16") (pintype "input"))
      (node (ref "DAC") (pin "5") (pinfunction "VREFL_5") (pintype "input"))
      (node (ref "DAC") (pin "6") (pinfunction "GND_6") (pintype "passive"))
      (node (ref "DOWNSW") (pin "1") (pinfunction "1_1") (pintype "passive"))
      (node (ref "DOWNSW") (pin "2") (pinfunction "2_2") (pintype "passive"))
      (node (ref "IC1") (pin "1") (pinfunction "GND_1") (pintype "input"))
      (node (ref "IC3") (pin "10") (pinfunction "+IN_10") (pintype "input"))
      (node (ref "IC3") (pin "11") (pinfunction "V-_11") (pintype "power_in"))
      (node (ref "IC3") (pin "12") (pinfunction "+IN_12") (pintype "input"))
      (node (ref "IC3") (pin "3") (pinfunction "+IN_3") (pintype "input"))
      (node (ref "IC3") (pin "5") (pinfunction "+IN_5") (pintype "input"))
      (node (ref "IC5") (pin "1") (pinfunction "C_1") (pintype "passive"))
      (node (ref "J2") (pin "2") (pinfunction "2_2") (pintype "passive"))
      (node (ref "J2") (pin "3") (pinfunction "3_3") (pintype "passive"))
      (node (ref "J3") (pin "2") (pinfunction "3_2") (pintype "bidirectional"))
      (node (ref "J3") (pin "3") (pinfunction "2_3") (pintype "bidirectional"))
      (node (ref "JP1") (pin "1") (pinfunction "1_1") (pintype "passive"))
      (node (ref "R15") (pin "1") (pinfunction "1_1") (pintype "passive"))
      (node (ref "R34") (pin "1") (pinfunction "1_1") (pintype "passive"))
      (node (ref "R36") (pin "1") (pinfunction "1_1") (pintype "passive"))
      (node (ref "R38") (pin "1") (pinfunction "1_1") (pintype "passive"))
      (node (ref "R40") (pin "1") (pinfunction "1_1") (pintype "passive"))
      (node (ref "SW_L") (pin "C") (pinfunction "C_C") (pintype "passive"))
      (node (ref "SW_L") (pin "D") (pinfunction "1_D") (pintype "passive"))
      (node (ref "SW_R") (pin "C") (pinfunction "C_C") (pintype "passive"))
      (node (ref "SW_R") (pin "D") (pinfunction "1_D") (pintype "passive"))
      (node (ref "T1") (pin "E") (pinfunction "E_E") (pintype "passive"))
      (node (ref "T2") (pin "E") (pinfunction "E_E") (pintype "passive"))
      (node (ref "T3") (pin "E") (pinfunction "E_E") (pintype "passive"))
      (node (ref "T4") (pin "E") (pinfunction "E_E") (pintype "passive"))
      (node (ref "TEENSY3.2") (pin "AGND") (pinfunction "AGND_AGND") (pintype "power_in"))
      (node (ref "TEENSY3.2") (pin "GND") (pinfunction "GND_GND") (pintype "power_in"))
      (node (ref "U1") (pin "1") (pinfunction "GND_1") (pintype "passive"))
      (node (ref "U2") (pin "2") (pinfunction "GND_2") (pintype "bidirectional"))
      (node (ref "UPSW") (pin "1") (pinfunction "1_1") (pintype "passive"))
      (node (ref "UPSW") (pin "2") (pinfunction "2_2") (pintype "passive"))
    )
    (net (code "23") (name "Net-(A-1)") (class "Default")
      (node (ref "A") (pin "P$1") (pinfunction "1_P$1") (pintype "passive"))
      (node (ref "CV_A") (pin "1") (pinfunction "1_1") (pintype "passive"))
      (node (ref "R8") (pin "2") (pinfunction "2_2") (pintype "passive"))
      (node (ref "R9") (pin "2") (pinfunction "2_2") (pintype "passive"))
    )
    (net (code "24") (name "Net-(B-1)") (class "Default")
      (node (ref "B") (pin "P$1") (pinfunction "1_P$1") (pintype "passive"))
      (node (ref "CV_B") (pin "1") (pinfunction "1_1") (pintype "passive"))
      (node (ref "R11") (pin "2") (pinfunction "2_2") (pintype "passive"))
      (node (ref "R12") (pin "2") (pinfunction "2_2") (pintype "passive"))
    )
    (net (code "25") (name "Net-(C-1)") (class "Default")
      (node (ref "C") (pin "P$1") (pinfunction "1_P$1") (pintype "passive"))
      (node (ref "CV_C") (pin "1") (pinfunction "1_1") (pintype "passive"))
      (node (ref "R2") (pin "2") (pinfunction "2_2") (pintype "passive"))
      (node (ref "R3") (pin "2") (pinfunction "2_2") (pintype "passive"))
    )
    (net (code "26") (name "Net-(CV1-1)") (class "Default")
      (node (ref "CV1") (pin "P$1") (pinfunction "1_P$1") (pintype "passive"))
      (node (ref "CVIN1") (pin "1") (pinfunction "1_1") (pintype "passive"))
      (node (ref "R18") (pin "1") (pinfunction "1_1") (pintype "passive"))
    )
    (net (code "27") (name "Net-(CV2-1)") (class "Default")
      (node (ref "CV2") (pin "P$1") (pinfunction "1_P$1") (pintype "passive"))
      (node (ref "CVIN2") (pin "1") (pinfunction "1_1") (pintype "passive"))
      (node (ref "R22") (pin "1") (pinfunction "1_1") (pintype "passive"))
    )
    (net (code "28") (name "Net-(CV3-1)") (class "Default")
      (node (ref "CV3") (pin "P$1") (pinfunction "1_P$1") (pintype "passive"))
      (node (ref "CVIN3") (pin "1") (pinfunction "1_1") (pintype "passive"))
      (node (ref "R26") (pin "1") (pinfunction "1_1") (pintype "passive"))
    )
    (net (code "29") (name "Net-(CV4-1)") (class "Default")
      (node (ref "CV4") (pin "P$1") (pinfunction "1_P$1") (pintype "passive"))
      (node (ref "CVIN4") (pin "1") (pinfunction "1_1") (pintype "passive"))
      (node (ref "R30") (pin "1") (pinfunction "1_1") (pintype "passive"))
    )
    (net (code "30") (name "Net-(D-1)") (class "Default")
      (node (ref "CV_D") (pin "1") (pinfunction "1_1") (pintype "passive"))
      (node (ref "D") (pin "P$1") (pinfunction "1_P$1") (pintype "passive"))
      (node (ref "R5") (pin "2") (pinfunction "2_2") (pintype "passive"))
      (node (ref "R6") (pin "2") (pinfunction "2_2") (pintype "passive"))
    )
    (net (code "31") (name "Net-(D1-PadC)") (class "Default")
      (node (ref "D1") (pin "C") (pinfunction "C_C") (pintype "passive"))
      (node (ref "R39") (pin "2") (pinfunction "2_2") (pintype "passive"))
      (node (ref "R40") (pin "2") (pinfunction "2_2") (pintype "passive"))
      (node (ref "T4") (pin "B") (pinfunction "B_B") (pintype "passive"))
    )
    (net (code "32") (name "Net-(D2-PadC)") (class "Default")
      (node (ref "D2") (pin "C") (pinfunction "C_C") (pintype "passive"))
      (node (ref "R37") (pin "2") (pinfunction "2_2") (pintype "passive"))
      (node (ref "R38") (pin "2") (pinfunction "2_2") (pintype "passive"))
      (node (ref "T3") (pin "B") (pinfunction "B_B") (pintype "passive"))
    )
    (net (code "33") (name "Net-(D3-PadC)") (class "Default")
      (node (ref "D3") (pin "C") (pinfunction "C_C") (pintype "passive"))
      (node (ref "R35") (pin "2") (pinfunction "2_2") (pintype "passive"))
      (node (ref "R36") (pin "2") (pinfunction "2_2") (pintype "passive"))
      (node (ref "T2") (pin "B") (pinfunction "B_B") (pintype "passive"))
    )
    (net (code "34") (name "Net-(D4-PadC)") (class "Default")
      (node (ref "D4") (pin "C") (pinfunction "C_C") (pintype "passive"))
      (node (ref "R33") (pin "2") (pinfunction "2_2") (pintype "passive"))
      (node (ref "R34") (pin "2") (pinfunction "2_2") (pintype "passive"))
      (node (ref "T1") (pin "B") (pinfunction "B_B") (pintype "passive"))
    )
    (net (code "35") (name "Net-(DOWNSW-Pad3)") (class "Default")
      (node (ref "DOWNSW") (pin "3") (pinfunction "3_3") (pintype "passive"))
      (node (ref "DOWNSW") (pin "4") (pinfunction "4_4") (pintype "passive"))
      (node (ref "R42") (pin "1") (pinfunction "1_1") (pintype "passive"))
    )
    (net (code "36") (name "Net-(IC1-OUT)") (class "Default")
      (node (ref "C6") (pin "1") (pinfunction "1_1") (pintype "passive"))
      (node (ref "IC1") (pin "3") (pinfunction "OUT_3") (pintype "passive"))
      (node (ref "L1") (pin "1") (pinfunction "1_1") (pintype "passive"))
    )
    (net (code "37") (name "Net-(IC3A--IN)") (class "Default")
      (node (ref "C20") (pin "1") (pinfunction "1_1") (pintype "passive"))
      (node (ref "IC3") (pin "2") (pinfunction "-IN_2") (pintype "input"))
      (node (ref "R24") (pin "1") (pinfunction "1_1") (pintype "passive"))
      (node (ref "R26") (pin "2") (pinfunction "2_2") (pintype "passive"))
      (node (ref "R27") (pin "2") (pinfunction "2_2") (pintype "passive"))
    )
    (net (code "38") (name "Net-(IC3A-OUT)") (class "Default")
      (node (ref "C20") (pin "2") (pinfunction "2_2") (pintype "passive"))
      (node (ref "IC3") (pin "1") (pinfunction "OUT_1") (pintype "output"))
      (node (ref "R24") (pin "2") (pinfunction "2_2") (pintype "passive"))
      (node (ref "R25") (pin "1") (pinfunction "1_1") (pintype "passive"))
    )
    (net (code "39") (name "Net-(IC3B--IN)") (class "Default")
      (node (ref "C19") (pin "1") (pinfunction "1_1") (pintype "passive"))
      (node (ref "IC3") (pin "6") (pinfunction "-IN_6") (pintype "input"))
      (node (ref "R20") (pin "1") (pinfunction "1_1") (pintype "passive"))
      (node (ref "R22") (pin "2") (pinfunction "2_2") (pintype "passive"))
      (node (ref "R23") (pin "2") (pinfunction "2_2") (pintype "passive"))
    )
    (net (code "40") (name "Net-(IC3B-OUT)") (class "Default")
      (node (ref "C19") (pin "2") (pinfunction "2_2") (pintype "passive"))
      (node (ref "IC3") (pin "7") (pinfunction "OUT_7") (pintype "output"))
      (node (ref "R20") (pin "2") (pinfunction "2_2") (pintype "passive"))
      (node (ref "R21") (pin "1") (pinfunction "1_1") (pintype "passive"))
    )
    (net (code "41") (name "Net-(IC3C--IN)") (class "Default")
      (node (ref "C18") (pin "1") (pinfunction "1_1") (pintype "passive"))
      (node (ref "IC3") (pin "9") (pinfunction "-IN_9") (pintype "input"))
      (node (ref "R16") (pin "1") (pinfunction "1_1") (pintype "passive"))
      (node (ref "R18") (pin "2") (pinfunction "2_2") (pintype "passive"))
      (node (ref "R19") (pin "2") (pinfunction "2_2") (pintype "passive"))
    )
    (net (code "42") (name "Net-(IC3C-OUT)") (class "Default")
      (node (ref "C18") (pin "2") (pinfunction "2_2") (pintype "passive"))
      (node (ref "IC3") (pin "8") (pinfunction "OUT_8") (pintype "output"))
      (node (ref "R16") (pin "2") (pinfunction "2_2") (pintype "passive"))
      (node (ref "R17") (pin "1") (pinfunction "1_1") (pintype "passive"))
    )
    (net (code "43") (name "Net-(IC3D--IN)") (class "Default")
      (node (ref "C21") (pin "1") (pinfunction "1_1") (pintype "passive"))
      (node (ref "IC3") (pin "13") (pinfunction "-IN_13") (pintype "input"))
      (node (ref "R28") (pin "1") (pinfunction "1_1") (pintype "passive"))
      (node (ref "R30") (pin "2") (pinfunction "2_2") (pintype "passive"))
      (node (ref "R31") (pin "2") (pinfunction "2_2") (pintype "passive"))
    )
    (net (code "44") (name "Net-(IC3D-OUT)") (class "Default")
      (node (ref "C21") (pin "2") (pinfunction "2_2") (pintype "passive"))
      (node (ref "IC3") (pin "14") (pinfunction "OUT_14") (pintype "output"))
      (node (ref "R28") (pin "2") (pinfunction "2_2") (pintype "passive"))
      (node (ref "R29") (pin "1") (pinfunction "1_1") (pintype "passive"))
    )
    (net (code "45") (name "Net-(IC7A--IN)") (class "Default")
      (node (ref "C12") (pin "1") (pinfunction "1_1") (pintype "passive"))
      (node (ref "IC7") (pin "2") (pinfunction "-IN_2") (pintype "input"))
      (node (ref "R10") (pin "2") (pinfunction "2_2") (pintype "passive"))
      (node (ref "R9") (pin "1") (pinfunction "1_1") (pintype "passive"))
    )
    (net (code "46") (name "Net-(IC7A-OUT)") (class "Default")
      (node (ref "C12") (pin "2") (pinfunction "2_2") (pintype "passive"))
      (node (ref "IC7") (pin "1") (pinfunction "OUT_1") (pintype "output"))
      (node (ref "R8") (pin "1") (pinfunction "1_1") (pintype "passive"))
    )
    (net (code "47") (name "Net-(IC7B--IN)") (class "Default")
      (node (ref "C10") (pin "1") (pinfunction "1_1") (pintype "passive"))
      (node (ref "IC7") (pin "6") (pinfunction "-IN_6") (pintype "input"))
      (node (ref "R3") (pin "1") (pinfunction "1_1") (pintype "passive"))
      (node (ref "R4") (pin "2") (pinfunction "2_2") (pintype "passive"))
    )
    (net (code "48") (name "Net-(IC7B-OUT)") (class "Default")
      (node (ref "C10") (pin "2") (pinfunction "2_2") (pintype "passive"))
      (node (ref "IC7") (pin "7") (pinfunction "OUT_7") (pintype "output"))
      (node (ref "R2") (pin "1") (pinfunction "1_1") (pintype "passive"))
    )
    (net (code "49") (name "Net-(IC7C--IN)") (class "Default")
      (node (ref "C11") (pin "1") (pinfunction "1_1") (pintype "passive"))
      (node (ref "IC7") (pin "9") (pinfunction "-IN_9") (pintype "input"))
      (node (ref "R6") (pin "1") (pinfunction "1_1") (pintype "passive"))
      (node (ref "R7") (pin "2") (pinfunction "2_2") (pintype "passive"))
    )
    (net (code "50") (name "Net-(IC7C-OUT)") (class "Default")
      (node (ref "C11") (pin "2") (pinfunction "2_2") (pintype "passive"))
      (node (ref "IC7") (pin "8") (pinfunction "OUT_8") (pintype "output"))
      (node (ref "R5") (pin "1") (pinfunction "1_1") (pintype "passive"))
    )
    (net (code "51") (name "Net-(IC7D--IN)") (class "Default")
      (node (ref "C13") (pin "1") (pinfunction "1_1") (pintype "passive"))
      (node (ref "IC7") (pin "13") (pinfunction "-IN_13") (pintype "input"))
      (node (ref "R12") (pin "1") (pinfunction "1_1") (pintype "passive"))
      (node (ref "R13") (pin "2") (pinfunction "2_2") (pintype "passive"))
    )
    (net (code "52") (name "Net-(IC7D-OUT)") (class "Default")
      (node (ref "C13") (pin "2") (pinfunction "2_2") (pintype "passive"))
      (node (ref "IC7") (pin "14") (pinfunction "OUT_14") (pintype "output"))
      (node (ref "R11") (pin "1") (pinfunction "1_1") (pintype "passive"))
    )
    (net (code "53") (name "Net-(J3-1)") (class "Default")
      (node (ref "D11") (pin "C") (pinfunction "C_C") (pintype "passive"))
      (node (ref "J2") (pin "4") (pinfunction "4_4") (pintype "passive"))
      (node (ref "J3") (pin "4") (pinfunction "1_4") (pintype "bidirectional"))
    )
    (net (code "54") (name "Net-(J3-4)") (class "Default")
      (node (ref "D9") (pin "A") (pinfunction "A_A") (pintype "passive"))
      (node (ref "J2") (pin "1") (pinfunction "1_1") (pintype "passive"))
      (node (ref "J3") (pin "1") (pinfunction "4_1") (pintype "bidirectional"))
    )
    (net (code "55") (name "Net-(R41-Pad1)") (class "Default")
      (node (ref "R41") (pin "1") (pinfunction "1_1") (pintype "passive"))
      (node (ref "UPSW") (pin "3") (pinfunction "3_3") (pintype "passive"))
      (node (ref "UPSW") (pin "4") (pinfunction "4_4") (pintype "passive"))
    )
    (net (code "56") (name "Net-(TRIG1-1)") (class "Default")
      (node (ref "R33") (pin "1") (pinfunction "1_1") (pintype "passive"))
      (node (ref "TR1") (pin "1") (pinfunction "1_1") (pintype "passive"))
      (node (ref "TRIG1") (pin "P$1") (pinfunction "1_P$1") (pintype "passive"))
    )
    (net (code "57") (name "Net-(TRIG2-1)") (class "Default")
      (node (ref "R35") (pin "1") (pinfunction "1_1") (pintype "passive"))
      (node (ref "TR2") (pin "1") (pinfunction "1_1") (pintype "passive"))
      (node (ref "TRIG2") (pin "P$1") (pinfunction "1_P$1") (pintype "passive"))
    )
    (net (code "58") (name "Net-(TRIG3-1)") (class "Default")
      (node (ref "R37") (pin "1") (pinfunction "1_1") (pintype "passive"))
      (node (ref "TR3") (pin "1") (pinfunction "1_1") (pintype "passive"))
      (node (ref "TRIG3") (pin "P$1") (pinfunction "1_P$1") (pintype "passive"))
    )
    (net (code "59") (name "Net-(TRIG4-1)") (class "Default")
      (node (ref "R39") (pin "1") (pinfunction "1_1") (pintype "passive"))
      (node (ref "TR4") (pin "1") (pinfunction "1_1") (pintype "passive"))
      (node (ref "TRIG4") (pin "P$1") (pinfunction "1_P$1") (pintype "passive"))
    )
    (net (code "60") (name "OFFSET") (class "Default")
      (node (ref "C22") (pin "1") (pinfunction "1_1") (pintype "passive"))
      (node (ref "IC5") (pin "2") (pinfunction "A_2") (pintype "passive"))
      (node (ref "R19") (pin "1") (pinfunction "1_1") (pintype "passive"))
      (node (ref "R23") (pin "1") (pinfunction "1_1") (pintype "passive"))
      (node (ref "R27") (pin "1") (pinfunction "1_1") (pintype "passive"))
      (node (ref "R31") (pin "1") (pinfunction "1_1") (pintype "passive"))
      (node (ref "R32") (pin "1") (pinfunction "1_1") (pintype "passive"))
    )
    (net (code "61") (name "POGO") (class "Default")
      (node (ref "R43") (pin "1") (pinfunction "1_1") (pintype "passive"))
      (node (ref "U1") (pin "2") (pinfunction "~{RESET}_2") (pintype "passive"))
    )
    (net (code "62") (name "RST") (class "Default")
      (node (ref "JP1") (pin "5") (pinfunction "5_5") (pintype "passive"))
      (node (ref "TEENSY3.2") (pin "7") (pinfunction "7/RX3_7") (pintype "bidirectional"))
    )
    (net (code "63") (name "RST_DAC") (class "Default")
      (node (ref "DAC") (pin "13") (pinfunction "~{RST}_13") (pintype "input"))
      (node (ref "TEENSY3.2") (pin "9") (pinfunction "9/RX2/PWM_9") (pintype "bidirectional"))
    )
    (net (code "64") (name "SCK") (class "Default")
      (node (ref "DAC") (pin "10") (pinfunction "SCLK_10") (pintype "input"))
      (node (ref "JP1") (pin "3") (pinfunction "3_3") (pintype "passive"))
      (node (ref "TEENSY3.2") (pin "13") (pinfunction "13/SCK/LED_13") (pintype "bidirectional"))
    )
    (net (code "65") (name "SW_B") (class "Default")
      (node (ref "C24") (pin "1") (pinfunction "1_1") (pintype "passive"))
      (node (ref "R42") (pin "2") (pinfunction "2_2") (pintype "passive"))
      (node (ref "TEENSY3.2") (pin "4") (pinfunction "4/CAN-RX/PWM_4") (pintype "bidirectional"))
    )
    (net (code "66") (name "SW_L") (class "Default")
      (node (ref "C17") (pin "1") (pinfunction "1_1") (pintype "passive"))
      (node (ref "SW_L") (pin "E") (pinfunction "2_E") (pintype "passive"))
      (node (ref "TEENSY3.2") (pin "23/A9") (pinfunction "23/A9/T/PWM_23/A9") (pintype "bidirectional"))
    )
    (net (code "67") (name "SW_R") (class "Default")
      (node (ref "SW_R") (pin "E") (pinfunction "2_E") (pintype "passive"))
      (node (ref "TEENSY3.2") (pin "14/A0") (pinfunction "14/A1_14/A0") (pintype "bidirectional"))
    )
    (net (code "68") (name "SW_T") (class "Default")
      (node (ref "C25") (pin "2") (pinfunction "2_2") (pintype "passive"))
      (node (ref "R41") (pin "2") (pinfunction "2_2") (pintype "passive"))
      (node (ref "TEENSY3.2") (pin "5") (pinfunction "5/PWM_5") (pintype "bidirectional"))
    )
    (net (code "69") (name "TR1") (class "Default")
      (node (ref "T1") (pin "C") (pinfunction "C_C") (pintype "passive"))
      (node (ref "TEENSY3.2") (pin "0") (pinfunction "0/RX1/T_0") (pintype "bidirectional"))
    )
    (net (code "70") (name "TR2") (class "Default")
      (node (ref "T2") (pin "C") (pinfunction "C_C") (pintype "passive"))
      (node (ref "TEENSY3.2") (pin "1") (pinfunction "1/TX1/T_1") (pintype "bidirectional"))
    )
    (net (code "71") (name "TR3") (class "Default")
      (node (ref "T3") (pin "C") (pinfunction "C_C") (pintype "passive"))
      (node (ref "TEENSY3.2") (pin "2") (pinfunction "2_2") (pintype "bidirectional"))
    )
    (net (code "72") (name "TR4") (class "Default")
      (node (ref "T4") (pin "C") (pinfunction "C_C") (pintype "passive"))
      (node (ref "TEENSY3.2") (pin "3") (pinfunction "3/CAN-TX/PWM_3") (pintype "bidirectional"))
    )
    (net (code "73") (name "UNUSED") (class "Default")
      (node (ref "TEENSY3.2") (pin "12") (pinfunction "12/MISO_12") (pintype "bidirectional"))
    )
    (net (code "74") (name "VREF_2V5") (class "Default")
      (node (ref "C14") (pin "1") (pinfunction "1_1") (pintype "passive"))
      (node (ref "C15") (pin "1") (pinfunction "1_1") (pintype "passive"))
      (node (ref "DAC") (pin "3") (pinfunction "VREFH/VREFOUT_3") (pintype "bidirectional"))
      (node (ref "R14") (pin "2") (pinfunction "2_2") (pintype "passive"))
    )
    (net (code "75") (name "V_BIAS") (class "Default")
      (node (ref "C16") (pin "1") (pinfunction "1_1") (pintype "passive"))
      (node (ref "IC7") (pin "10") (pinfunction "+IN_10") (pintype "input"))
      (node (ref "IC7") (pin "12") (pinfunction "+IN_12") (pintype "input"))
      (node (ref "IC7") (pin "3") (pinfunction "+IN_3") (pintype "input"))
      (node (ref "IC7") (pin "5") (pinfunction "+IN_5") (pintype "input"))
      (node (ref "R14") (pin "1") (pinfunction "1_1") (pintype "passive"))
      (node (ref "R15") (pin "2") (pinfunction "2_2") (pintype "passive"))
    )
  )
)
